# M5_STACK_STAMP_C3_ISOBUS.net
KiCad netlist of a schematic drawn in EAGLE
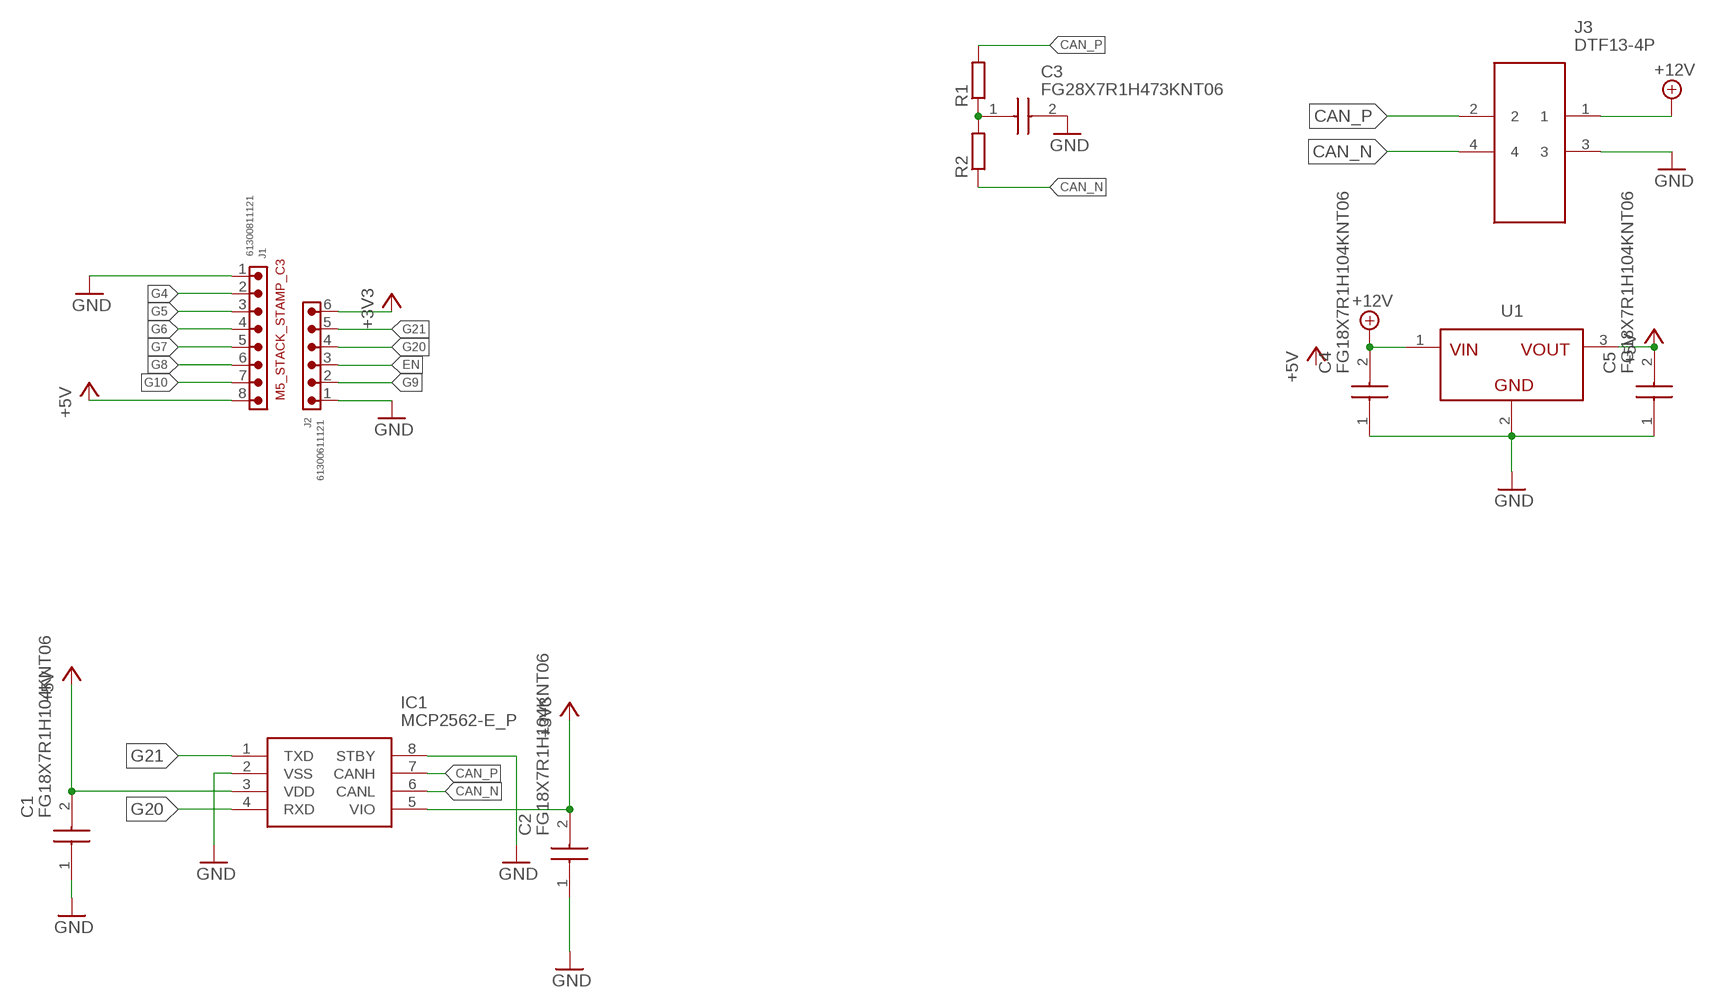
[diagram p0: schematic, sheet 1]

(export (version "E")
  (design (tool "Eeschema 10.0.6"))
  (components
    (comp (ref "C1")
      (value "FG18X7R1H104KNT06")
      (footprint "eagle-import:FG18C0G1H101JNT06")
      (fields (field (name "MOUSER_PART_NUMBER") "810-FG18X7R1H104KNT6"))
      (libsource (lib "eagle-import") (part "FG18X7R1H104KNT06"))
    )
    (comp (ref "C2")
      (value "FG18X7R1H104KNT06")
      (footprint "eagle-import:FG18C0G1H101JNT06")
      (fields (field (name "MOUSER_PART_NUMBER") "810-FG18X7R1H104KNT6"))
      (libsource (lib "eagle-import") (part "FG18X7R1H104KNT06"))
    )
    (comp (ref "C3")
      (value "FG28X7R1H473KNT06")
      (footprint "eagle-import:FG28")
      (fields (field (name "MOUSER_PART_NUMBER") "810-FG28X7R1H473KNT6"))
      (libsource (lib "eagle-import") (part "FG28X7R1H473KNT06"))
    )
    (comp (ref "C4")
      (value "FG18X7R1H104KNT06")
      (footprint "eagle-import:FG18C0G1H101JNT06")
      (fields (field (name "MOUSER_PART_NUMBER") "810-FG18X7R1H104KNT6"))
      (libsource (lib "eagle-import") (part "FG18X7R1H104KNT06"))
    )
    (comp (ref "C5")
      (value "FG18X7R1H104KNT06")
      (footprint "eagle-import:FG18C0G1H101JNT06")
      (fields (field (name "MOUSER_PART_NUMBER") "810-FG18X7R1H104KNT6"))
      (libsource (lib "eagle-import") (part "FG18X7R1H104KNT06"))
    )
    (comp (ref "IC1")
      (value "MCP2562-E_P")
      (footprint "eagle-import:DIP781W56P254L950H533Q8N")
      (fields
        (field (name "MANUFACTURER_PART_NUMBER") "MCP2562-E/P")
        (field (name "MOUSER_PART_NUMBER") "579-MCP2562-E/P")
      )
      (libsource (lib "eagle-import") (part "MCP2562-E_P"))
    )
    (comp (ref "J1")
      (value "61300811121")
      (footprint "eagle-import:61300811121")
      (libsource (lib "eagle-import") (part "6130XX11121_61300811121"))
    )
    (comp (ref "J2")
      (value "61300611121")
      (footprint "eagle-import:61300611121")
      (libsource (lib "eagle-import") (part "6130XX11121_61300611121"))
    )
    (comp (ref "J3")
      (value "DTF13-4P")
      (footprint "eagle-import:DTF134P")
      (fields (field (name "MOUSER_PART_NUMBER") "571-DTF13-4P"))
      (libsource (lib "eagle-import") (part "DTF13-4P"))
    )
    (comp (ref "R1")
      (value "R-EU_0204/7")
      (footprint "eagle-import:0204_7")
      (libsource (lib "eagle-import") (part "R-EU_0204/7"))
    )
    (comp (ref "R2")
      (value "R-EU_0204/7")
      (footprint "eagle-import:0204_7")
      (libsource (lib "eagle-import") (part "R-EU_0204/7"))
    )
    (comp (ref "U$1")
      (value "M5_STACK_STAMP_C3")
      (footprint "eagle-import:M5_STACK_STAMP_C3")
      (libsource (lib "eagle-import") (part "M5_STACK_STAMP_C3"))
    )
    (comp (ref "U1")
      (value "MAGI³C-FDSM_SIP-3_173010542_173XXXX42")
      (footprint "eagle-import:MAGI³C-FDSM_173XXXX42")
      (libsource (lib "eagle-import") (part "MAGI³C-FDSM_SIP-3_173XXXX42_173010542"))
    )
  )
  (nets
    (net (code "1") (name "+3V3") (class "Default")
      (node (ref "C2") (pin "2") (pinfunction "2_2") (pintype "bidirectional"))
      (node (ref "IC1") (pin "5") (pinfunction "VIO_5") (pintype "bidirectional"))
      (node (ref "J2") (pin "6") (pinfunction "6_6") (pintype "passive"))
    )
    (net (code "2") (name "+5V") (class "Default")
      (node (ref "C1") (pin "2") (pinfunction "2_2") (pintype "bidirectional"))
      (node (ref "C5") (pin "2") (pinfunction "2_2") (pintype "bidirectional"))
      (node (ref "IC1") (pin "3") (pinfunction "VDD_3") (pintype "bidirectional"))
      (node (ref "J1") (pin "8") (pinfunction "8_8") (pintype "passive"))
      (node (ref "U1") (pin "3") (pinfunction "VOUT_3") (pintype "output"))
    )
    (net (code "3") (name "+12V") (class "Default")
      (node (ref "C4") (pin "2") (pinfunction "2_2") (pintype "bidirectional"))
      (node (ref "J3") (pin "1") (pinfunction "1_1") (pintype "bidirectional"))
      (node (ref "U1") (pin "1") (pinfunction "VIN_1") (pintype "input"))
    )
    (net (code "4") (name "CAN_N") (class "Default")
      (node (ref "IC1") (pin "6") (pinfunction "CANL_6") (pintype "bidirectional"))
      (node (ref "J3") (pin "4") (pinfunction "4_4") (pintype "bidirectional"))
      (node (ref "R2") (pin "1") (pinfunction "1_1") (pintype "passive"))
    )
    (net (code "5") (name "CAN_P") (class "Default")
      (node (ref "IC1") (pin "7") (pinfunction "CANH_7") (pintype "bidirectional"))
      (node (ref "J3") (pin "2") (pinfunction "2_2") (pintype "bidirectional"))
      (node (ref "R1") (pin "2") (pinfunction "2_2") (pintype "passive"))
    )
    (net (code "6") (name "EN") (class "Default")
      (node (ref "J2") (pin "3") (pinfunction "3_3") (pintype "passive"))
    )
    (net (code "7") (name "G4") (class "Default")
      (node (ref "J1") (pin "2") (pinfunction "2_2") (pintype "passive"))
    )
    (net (code "8") (name "G5") (class "Default")
      (node (ref "J1") (pin "3") (pinfunction "3_3") (pintype "passive"))
    )
    (net (code "9") (name "G6") (class "Default")
      (node (ref "J1") (pin "4") (pinfunction "4_4") (pintype "passive"))
    )
    (net (code "10") (name "G7") (class "Default")
      (node (ref "J1") (pin "5") (pinfunction "5_5") (pintype "passive"))
    )
    (net (code "11") (name "G8") (class "Default")
      (node (ref "J1") (pin "6") (pinfunction "6_6") (pintype "passive"))
    )
    (net (code "12") (name "G9") (class "Default")
      (node (ref "J2") (pin "2") (pinfunction "2_2") (pintype "passive"))
    )
    (net (code "13") (name "G10") (class "Default")
      (node (ref "J1") (pin "7") (pinfunction "7_7") (pintype "passive"))
    )
    (net (code "14") (name "G20") (class "Default")
      (node (ref "IC1") (pin "4") (pinfunction "RXD_4") (pintype "bidirectional"))
      (node (ref "J2") (pin "4") (pinfunction "4_4") (pintype "passive"))
    )
    (net (code "15") (name "G21") (class "Default")
      (node (ref "IC1") (pin "1") (pinfunction "TXD_1") (pintype "bidirectional"))
      (node (ref "J2") (pin "5") (pinfunction "5_5") (pintype "passive"))
    )
    (net (code "16") (name "GND") (class "Default")
      (node (ref "C1") (pin "1") (pinfunction "1_1") (pintype "bidirectional"))
      (node (ref "C2") (pin "1") (pinfunction "1_1") (pintype "bidirectional"))
      (node (ref "C3") (pin "2") (pinfunction "2_2") (pintype "bidirectional"))
      (node (ref "C4") (pin "1") (pinfunction "1_1") (pintype "bidirectional"))
      (node (ref "C5") (pin "1") (pinfunction "1_1") (pintype "bidirectional"))
      (node (ref "IC1") (pin "2") (pinfunction "VSS_2") (pintype "bidirectional"))
      (node (ref "IC1") (pin "8") (pinfunction "STBY_8") (pintype "bidirectional"))
      (node (ref "J1") (pin "1") (pinfunction "1_1") (pintype "passive"))
      (node (ref "J2") (pin "1") (pinfunction "1_1") (pintype "passive"))
      (node (ref "J3") (pin "3") (pinfunction "3_3") (pintype "bidirectional"))
      (node (ref "U1") (pin "2") (pinfunction "GND_2") (pintype "passive"))
    )
    (net (code "17") (name "Net-(C3-Pad1)") (class "Default")
      (node (ref "C3") (pin "1") (pinfunction "1_1") (pintype "bidirectional"))
      (node (ref "R1") (pin "1") (pinfunction "1_1") (pintype "passive"))
      (node (ref "R2") (pin "2") (pinfunction "2_2") (pintype "passive"))
    )
  )
)
